# Rocket_PCB_Final.net
KiCad netlist of a schematic drawn in EasyEDA Pro
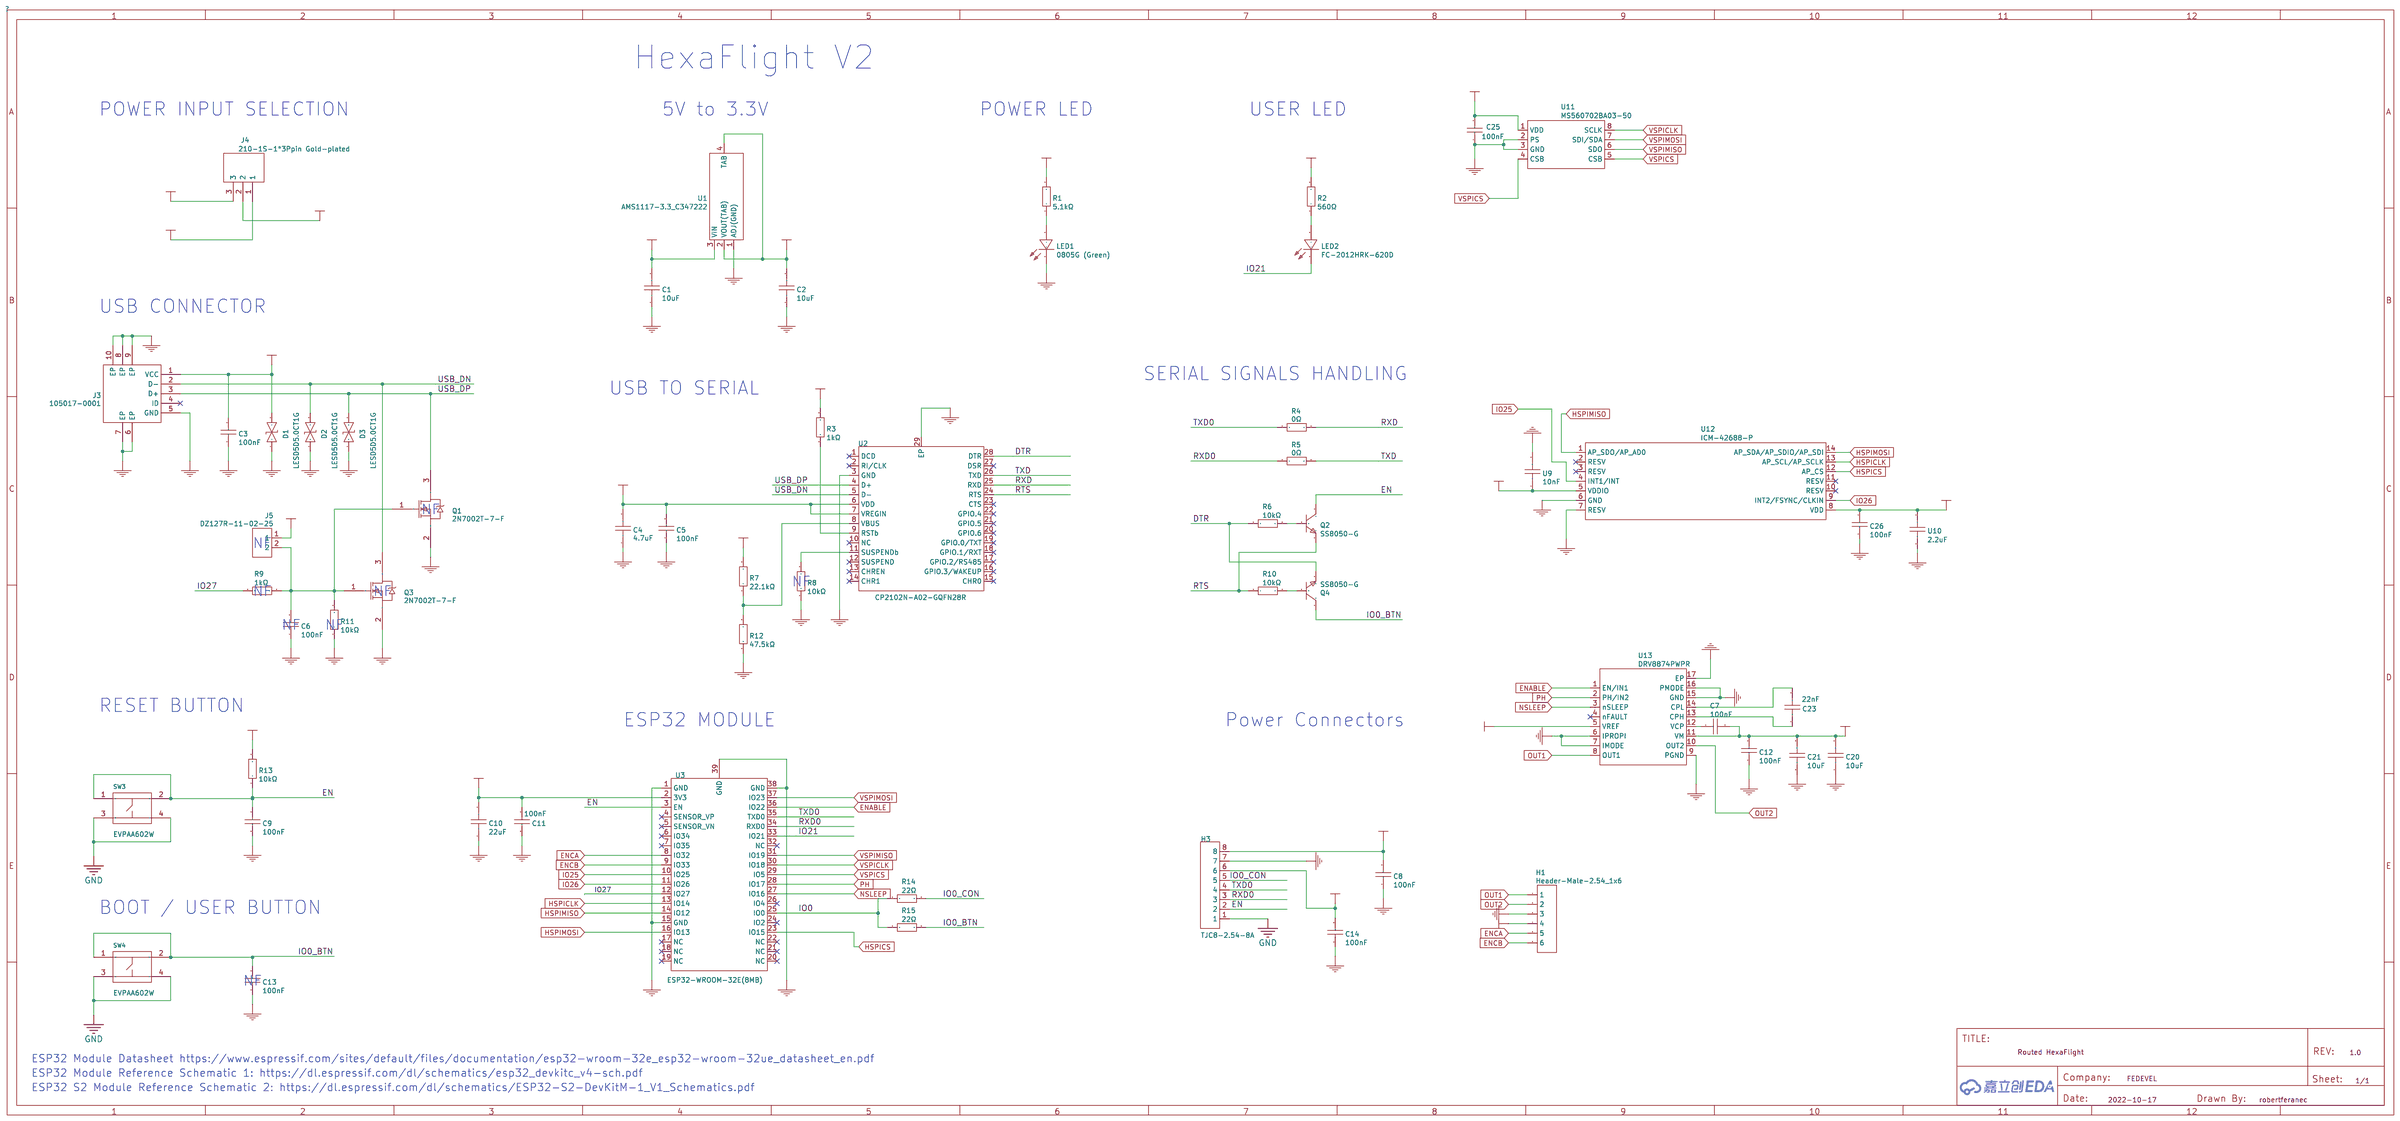
[diagram p0: schematic sheet]

(export (version "E")
  (design (tool "Eeschema 10.0.6"))
  (components
    (comp (ref "C1")
      (value "10uF")
      (footprint "easyedapro:C0402")
      (fields
        (field (name "Manufacturer Part") "CL05A106MP5NUNC")
        (field (name "Manufacturer") "Samsung Electro-Mechanics")
      )
      (libsource (lib "easyedapro") (part "10uF"))
    )
    (comp (ref "C2")
      (value "10uF")
      (footprint "easyedapro:C0402")
      (fields
        (field (name "Manufacturer Part") "CL05A106MP5NUNC")
        (field (name "Manufacturer") "Samsung Electro-Mechanics")
      )
      (libsource (lib "easyedapro") (part "10uF"))
    )
    (comp (ref "C3")
      (value "100nF")
      (footprint "easyedapro:C0402_NEW")
      (fields (field (name "Manufacturer Part") "CL05B104KO5NNNC") (field (name "Manufacturer") "SAMSUNG"))
      (libsource (lib "easyedapro") (part "100nF"))
    )
    (comp (ref "C4")
      (value "4.7uF")
      (footprint "easyedapro:C0402")
      (fields
        (field (name "Manufacturer Part") "CL05A475KP5NRNC")
        (field (name "Manufacturer") "Samsung Electro-Mechanics")
      )
      (libsource (lib "easyedapro") (part "4.7uF"))
    )
    (comp (ref "C5")
      (value "100nF")
      (footprint "easyedapro:C0402_NEW")
      (fields (field (name "Manufacturer Part") "CL05B104KO5NNNC") (field (name "Manufacturer") "SAMSUNG"))
      (libsource (lib "easyedapro") (part "100nF"))
    )
    (comp (ref "C6")
      (value "100nF")
      (footprint "easyedapro:C0402_NEW")
      (fields (field (name "Manufacturer Part") "CL05B104KO5NNNC") (field (name "Manufacturer") "SAMSUNG"))
      (libsource (lib "easyedapro") (part "100nF"))
    )
    (comp (ref "C7")
      (value "100nF")
      (footprint "easyedapro:C0402_NEW")
      (fields (field (name "Manufacturer Part") "CL05B104KO5NNNC") (field (name "Manufacturer") "SAMSUNG"))
      (libsource (lib "easyedapro") (part "100nF"))
    )
    (comp (ref "C8")
      (value "100nF")
      (footprint "easyedapro:C0402_NEW")
      (fields (field (name "Manufacturer Part") "CL05B104KO5NNNC") (field (name "Manufacturer") "SAMSUNG"))
      (libsource (lib "easyedapro") (part "100nF"))
    )
    (comp (ref "C9")
      (value "100nF")
      (footprint "easyedapro:C0402_NEW")
      (fields (field (name "Manufacturer Part") "CL05B104KO5NNNC") (field (name "Manufacturer") "SAMSUNG"))
      (libsource (lib "easyedapro") (part "100nF"))
    )
    (comp (ref "C10")
      (value "22uF")
      (footprint "easyedapro:C0805")
      (fields
        (field (name "Manufacturer Part") "CL21A226MAYNNNE")
        (field (name "Manufacturer") "Samsung Electro-Mechanics")
      )
      (libsource (lib "easyedapro") (part "22uF"))
    )
    (comp (ref "C11")
      (value "100nF")
      (footprint "easyedapro:C0402_NEW")
      (fields (field (name "Manufacturer Part") "CL05B104KO5NNNC") (field (name "Manufacturer") "SAMSUNG"))
      (libsource (lib "easyedapro") (part "100nF"))
    )
    (comp (ref "C12")
      (value "100nF")
      (footprint "easyedapro:C0402_NEW")
      (fields (field (name "Manufacturer Part") "CL05B104KO5NNNC") (field (name "Manufacturer") "SAMSUNG"))
      (libsource (lib "easyedapro") (part "100nF"))
    )
    (comp (ref "C13")
      (value "100nF")
      (footprint "easyedapro:C0402_NEW")
      (fields (field (name "Manufacturer Part") "CL05B104KO5NNNC") (field (name "Manufacturer") "SAMSUNG"))
      (libsource (lib "easyedapro") (part "100nF"))
    )
    (comp (ref "C14")
      (value "100nF")
      (footprint "easyedapro:C0402_NEW")
      (fields (field (name "Manufacturer Part") "CL05B104KO5NNNC") (field (name "Manufacturer") "SAMSUNG"))
      (libsource (lib "easyedapro") (part "100nF"))
    )
    (comp (ref "C20")
      (value "10uF")
      (footprint "easyedapro:C0402")
      (fields
        (field (name "Manufacturer Part") "CL05A106MP5NUNC")
        (field (name "Manufacturer") "Samsung Electro-Mechanics")
      )
      (libsource (lib "easyedapro") (part "10uF"))
    )
    (comp (ref "C21")
      (value "10uF")
      (footprint "easyedapro:C0402")
      (fields
        (field (name "Manufacturer Part") "CL05A106MP5NUNC")
        (field (name "Manufacturer") "Samsung Electro-Mechanics")
      )
      (libsource (lib "easyedapro") (part "10uF"))
    )
    (comp (ref "C23")
      (value "22nF")
      (footprint "easyedapro:C0603")
      (description "Capacitance:22nF Tolerance:±10% Tolerance:±10% Voltage Rating:50V Temperature Coefficient:X7R")
      (fields (field (name "Manufacturer Part") "CGA3E3X8R2A223KT0Y0N") (field (name "Manufacturer") "TDK"))
      (libsource (lib "easyedapro") (part "22nF"))
    )
    (comp (ref "C25")
      (value "100nF")
      (footprint "easyedapro:C0402_NEW")
      (fields (field (name "Manufacturer Part") "CL05B104KO5NNNC") (field (name "Manufacturer") "SAMSUNG"))
      (libsource (lib "easyedapro") (part "100nF"))
    )
    (comp (ref "C26")
      (value "100nF")
      (footprint "easyedapro:C0402_NEW")
      (fields (field (name "Manufacturer Part") "CL05B104KO5NNNC") (field (name "Manufacturer") "SAMSUNG"))
      (libsource (lib "easyedapro") (part "100nF"))
    )
    (comp (ref "D1")
      (value "LESD5D5.0CT1G")
      (footprint "easyedapro:SOD-523_L1.2-W0.8-LS1.6-BI")
      (fields (field (name "Manufacturer") "Leshan Radio") (field (name "Contributor") "LCSC"))
      (libsource (lib "easyedapro") (part "LESD5D5.0CT1G"))
    )
    (comp (ref "D2")
      (value "LESD5D5.0CT1G")
      (footprint "easyedapro:SOD-523_L1.2-W0.8-LS1.6-BI")
      (fields (field (name "Manufacturer") "Leshan Radio") (field (name "Contributor") "LCSC"))
      (libsource (lib "easyedapro") (part "LESD5D5.0CT1G"))
    )
    (comp (ref "D3")
      (value "LESD5D5.0CT1G")
      (footprint "easyedapro:SOD-523_L1.2-W0.8-LS1.6-BI")
      (fields (field (name "Manufacturer") "Leshan Radio") (field (name "Contributor") "LCSC"))
      (libsource (lib "easyedapro") (part "LESD5D5.0CT1G"))
    )
    (comp (ref "H1")
      (value "Header-Male-2.54_1x6")
      (footprint "easyedapro:HDR-TH_6P-P2.54-V-M-1")
      (fields (field (name "Manufacturer Part") "2.54-1x6P直针") (field (name "Manufacturer") "BOOMELE(博穆精密)"))
      (libsource (lib "easyedapro") (part "Header-Male-2.54_1x6"))
    )
    (comp (ref "H3")
      (value "TJC8-2.54-8A")
      (footprint "easyedapro:HDR-TH_8P-P2.54-V-M-4")
      (fields (field (name "Manufacturer") "DLL(德利)"))
      (libsource (lib "easyedapro") (part "TJC8-2.54-8A"))
    )
    (comp (ref "J3")
      (value "105017-0001")
      (footprint "easyedapro:MICRO-USB-SMD_105017-0001")
      (fields (field (name "Manufacturer") "MOLEX") (field (name "Contributor") "LCSC"))
      (libsource (lib "easyedapro") (part "105017-0001"))
    )
    (comp (ref "J4")
      (value "210-1S-1*3Ppin Gold-plated")
      (footprint "easyedapro:HDR-TH_3P-P1.27-V-M-1")
      (fields (field (name "Manufacturer") "Ckmtw") (field (name "Contributor") "LCSC"))
      (libsource (lib "easyedapro") (part "210-1S-1*3Ppin Gold-plated"))
    )
    (comp (ref "J5")
      (value "DZ127R-11-02-25")
      (footprint "easyedapro:HDR-TH_2P-P1.27-V-M")
      (fields (field (name "Manufacturer") "DEALON(德艺隆)") (field (name "Contributor") "LCSC"))
      (libsource (lib "easyedapro") (part "DZ127R-11-02-25"))
    )
    (comp (ref "LED1")
      (value "0805G (Green)")
      (footprint "easyedapro:LED0805-RD_GREEN")
      (fields (field (name "Manufacturer") "KENTO"))
      (libsource (lib "easyedapro") (part "0805G (Green)"))
    )
    (comp (ref "LED2")
      (value "FC-2012HRK-620D")
      (footprint "easyedapro:LED0805-RD_RED")
      (fields (field (name "Manufacturer") "NATIONSTAR"))
      (libsource (lib "easyedapro") (part "FC-2012HRK-620D"))
    )
    (comp (ref "Q1")
      (value "2N7002T-7-F")
      (footprint "easyedapro:SOT-523-3_L1.6-W0.8-P1.00-LS1.6-BR")
      (fields (field (name "Manufacturer") "DIODES") (field (name "Contributor") "LCSC"))
      (libsource (lib "easyedapro") (part "2N7002T-7-F"))
    )
    (comp (ref "Q2")
      (value "SS8050-G")
      (footprint "easyedapro:SOT-23-3_L2.9-W1.6-P1.90-LS2.8-BR")
      (fields (field (name "Manufacturer") "CJ(江苏长电/长晶)") (field (name "Contributor") "LCSC"))
      (libsource (lib "easyedapro") (part "SS8050-G"))
    )
    (comp (ref "Q3")
      (value "2N7002T-7-F")
      (footprint "easyedapro:SOT-523-3_L1.6-W0.8-P1.00-LS1.6-BR")
      (fields (field (name "Manufacturer") "DIODES") (field (name "Contributor") "LCSC"))
      (libsource (lib "easyedapro") (part "2N7002T-7-F"))
    )
    (comp (ref "Q4")
      (value "SS8050-G")
      (footprint "easyedapro:SOT-23-3_L2.9-W1.6-P1.90-LS2.8-BR")
      (fields (field (name "Manufacturer") "CJ(江苏长电/长晶)") (field (name "Contributor") "LCSC"))
      (libsource (lib "") (part "SS8050-G_1"))
    )
    (comp (ref "R1")
      (value "5.1kΩ")
      (footprint "easyedapro:R0402")
      (fields (field (name "Manufacturer Part") "0402WGF5101TCE") (field (name "Manufacturer") "UniOhm"))
      (libsource (lib "easyedapro") (part "5.1kΩ"))
    )
    (comp (ref "R2")
      (value "560Ω")
      (footprint "easyedapro:R0402")
      (fields (field (name "Manufacturer Part") "0402WGF5600TCE") (field (name "Manufacturer") "UniOhm"))
      (libsource (lib "easyedapro") (part "560Ω"))
    )
    (comp (ref "R3")
      (value "1kΩ")
      (footprint "easyedapro:R0402")
      (fields (field (name "Manufacturer Part") "0402WGF1001TCE") (field (name "Manufacturer") "UniOhm"))
      (libsource (lib "easyedapro") (part "1kΩ"))
    )
    (comp (ref "R4")
      (value "0Ω")
      (footprint "easyedapro:R0402")
      (fields (field (name "Manufacturer Part") "0402WGF0000TCE") (field (name "Manufacturer") "UniOhm"))
      (libsource (lib "easyedapro") (part "0Ω"))
    )
    (comp (ref "R5")
      (value "0Ω")
      (footprint "easyedapro:R0402")
      (fields (field (name "Manufacturer Part") "0402WGF0000TCE") (field (name "Manufacturer") "UniOhm"))
      (libsource (lib "easyedapro") (part "0Ω"))
    )
    (comp (ref "R6")
      (value "10kΩ")
      (footprint "easyedapro:R0402")
      (fields (field (name "Manufacturer Part") "0402WGF1002TCE") (field (name "Manufacturer") "UniOhm"))
      (libsource (lib "easyedapro") (part "10kΩ"))
    )
    (comp (ref "R7")
      (value "22.1kΩ")
      (footprint "easyedapro:R0402")
      (fields (field (name "Manufacturer Part") "0402WGF2212TCE") (field (name "Manufacturer") "UniOhm"))
      (libsource (lib "easyedapro") (part "22.1kΩ"))
    )
    (comp (ref "R8")
      (value "10kΩ")
      (footprint "easyedapro:R0402")
      (fields (field (name "Manufacturer Part") "0402WGF1002TCE") (field (name "Manufacturer") "UniOhm"))
      (libsource (lib "") (part "10kΩ_1"))
    )
    (comp (ref "R9")
      (value "1kΩ")
      (footprint "easyedapro:R0402")
      (fields (field (name "Manufacturer Part") "0402WGF1001TCE") (field (name "Manufacturer") "UniOhm"))
      (libsource (lib "") (part "1kΩ_1"))
    )
    (comp (ref "R10")
      (value "10kΩ")
      (footprint "easyedapro:R0402")
      (fields (field (name "Manufacturer Part") "0402WGF1002TCE") (field (name "Manufacturer") "UniOhm"))
      (libsource (lib "easyedapro") (part "10kΩ"))
    )
    (comp (ref "R11")
      (value "10kΩ")
      (footprint "easyedapro:R0402")
      (fields (field (name "Manufacturer Part") "0402WGF1002TCE") (field (name "Manufacturer") "UniOhm"))
      (libsource (lib "") (part "10kΩ_1"))
    )
    (comp (ref "R12")
      (value "47.5kΩ")
      (footprint "easyedapro:R0402")
      (fields (field (name "Manufacturer Part") "0402WGF4752TCE") (field (name "Manufacturer") "UniOhm"))
      (libsource (lib "easyedapro") (part "47.5kΩ"))
    )
    (comp (ref "R13")
      (value "10kΩ")
      (footprint "easyedapro:R0402")
      (fields (field (name "Manufacturer Part") "0402WGF1002TCE") (field (name "Manufacturer") "UniOhm"))
      (libsource (lib "") (part "10kΩ_1"))
    )
    (comp (ref "R14")
      (value "22Ω")
      (footprint "easyedapro:R0402")
      (fields (field (name "Manufacturer Part") "0402WGF220JTCE") (field (name "Manufacturer") "UniOhm"))
      (libsource (lib "easyedapro") (part "22Ω"))
    )
    (comp (ref "R15")
      (value "22Ω")
      (footprint "easyedapro:R0402")
      (fields (field (name "Manufacturer Part") "0402WGF220JTCE") (field (name "Manufacturer") "UniOhm"))
      (libsource (lib "easyedapro") (part "22Ω"))
    )
    (comp (ref "SW3")
      (value "EVPAA602W")
      (footprint "easyedapro:KEY-TH_4P-L3.5-W4.9-P2.80-LS4.3")
      (fields (field (name "Manufacturer") "PANASONIC(松下)"))
      (libsource (lib "easyedapro") (part "EVPAA602W"))
    )
    (comp (ref "SW4")
      (value "EVPAA602W")
      (footprint "easyedapro:KEY-TH_4P-L3.5-W4.9-P2.80-LS4.3")
      (fields (field (name "Manufacturer") "PANASONIC(松下)"))
      (libsource (lib "easyedapro") (part "EVPAA602W"))
    )
    (comp (ref "U1")
      (value "AMS1117-3.3_C347222")
      (footprint "easyedapro:SOT-223-4_L6.5-W3.5-P2.30-LS7.0-BR")
      (fields
        (field (name "Manufacturer Part") "AMS1117-3.3")
        (field (name "Manufacturer") "Youtai Semiconductor Co., Ltd.")
        (field (name "Contributor") "LCSC")
      )
      (libsource (lib "easyedapro") (part "AMS1117-3.3_C347222"))
    )
    (comp (ref "U2")
      (value "CP2102N-A02-GQFN28R")
      (footprint "easyedapro:QFN-28_L5.0-W5.0-P0.50-TL-EP3.3")
      (fields (field (name "Manufacturer") "SILICON LABS(芯科)") (field (name "Contributor") "LCSC"))
      (libsource (lib "easyedapro") (part "CP2102N-A02-GQFN28R"))
    )
    (comp (ref "U3")
      (value "ESP32-WROOM-32E(8MB)")
      (footprint "easyedapro:WIFI-SMD_ESP32-WROOM-32E")
      (fields (field (name "Manufacturer") "Espressif Systems") (field (name "Contributor") "LCSC"))
      (libsource (lib "easyedapro") (part "ESP32-WROOM-32E(8MB)"))
    )
    (comp (ref "U9")
      (value "10nF")
      (footprint "easyedapro:C0603")
      (fields
        (field (name "Manufacturer Part") "AC0603KRX7R7BB103")
        (field (name "Manufacturer") "YAGEO(国巨)")
      )
      (libsource (lib "easyedapro") (part "10nF"))
    )
    (comp (ref "U10")
      (value "2.2uF")
      (footprint "easyedapro:C0805")
      (fields
        (field (name "Manufacturer Part") "0805X225K250CT")
        (field (name "Manufacturer") "Walsin(华新科)")
        (field (name "Contributor") "lcsc")
      )
      (libsource (lib "easyedapro") (part "2.2uF"))
    )
    (comp (ref "U11")
      (value "MS560702BA03-50")
      (footprint "easyedapro:SENSOR-SMD_MS560702BA03-50")
      (fields (field (name "Manufacturer") "TE Connectivity(泰科电子)") (field (name "Contributor") "LCSC"))
      (libsource (lib "easyedapro") (part "MS560702BA03-50"))
    )
    (comp (ref "U12")
      (value "ICM-42688-P")
      (footprint "easyedapro:LGA-14_L3.0-W2.5-P0.50-TL")
      (fields (field (name "Manufacturer") "TDK InvenSense(应美盛)") (field (name "Contributor") "LCSC"))
      (libsource (lib "easyedapro") (part "ICM-42688-P"))
    )
    (comp (ref "U13")
      (value "DRV8874PWPR")
      (footprint "easyedapro:HTSSOP-16_L5.0-W4.4-P0.65-LS6.4-BL-EP")
      (fields (field (name "Manufacturer") "TI(德州仪器)") (field (name "Contributor") "LCSC"))
      (libsource (lib "easyedapro") (part "DRV8874PWPR"))
    )
  )
  (nets
    (net (code "1") (name "+3V3") (class "Default")
      (node (ref "C10") (pin "2") (pinfunction "2_2") (pintype "unspecified"))
      (node (ref "C11") (pin "2") (pinfunction "2_2") (pintype "input"))
      (node (ref "C2") (pin "2") (pinfunction "2_2") (pintype "unspecified"))
      (node (ref "C25") (pin "2") (pinfunction "2_2") (pintype "input"))
      (node (ref "C26") (pin "2") (pinfunction "2_2") (pintype "input"))
      (node (ref "C4") (pin "2") (pinfunction "2_2") (pintype "unspecified"))
      (node (ref "C5") (pin "2") (pinfunction "2_2") (pintype "input"))
      (node (ref "C8") (pin "2") (pinfunction "2_2") (pintype "input"))
      (node (ref "H3") (pin "8") (pinfunction "8_8") (pintype "unspecified"))
      (node (ref "J5") (pin "1") (pinfunction "1_1") (pintype "unspecified"))
      (node (ref "R1") (pin "2") (pinfunction "2_2") (pintype "input"))
      (node (ref "R13") (pin "2") (pinfunction "2_2") (pintype "input"))
      (node (ref "R2") (pin "2") (pinfunction "2_2") (pintype "input"))
      (node (ref "R3") (pin "2") (pinfunction "2_2") (pintype "input"))
      (node (ref "U1") (pin "2") (pinfunction "VOUT(TAB)_2") (pintype "unspecified"))
      (node (ref "U1") (pin "4") (pinfunction "TAB_4") (pintype "unspecified"))
      (node (ref "U10") (pin "1") (pinfunction "1_1") (pintype "unspecified"))
      (node (ref "U11") (pin "1") (pinfunction "VDD_1") (pintype "unspecified"))
      (node (ref "U12") (pin "5") (pinfunction "VDDIO_5") (pintype "unspecified"))
      (node (ref "U12") (pin "8") (pinfunction "VDD_8") (pintype "unspecified"))
      (node (ref "U13") (pin "5") (pinfunction "VREF_5") (pintype "unspecified"))
      (node (ref "U2") (pin "6") (pinfunction "VDD_6") (pintype "unspecified"))
      (node (ref "U2") (pin "7") (pinfunction "VREGIN_7") (pintype "unspecified"))
      (node (ref "U3") (pin "2") (pinfunction "3V3_2") (pintype "unspecified"))
      (node (ref "U9") (pin "1") (pinfunction "1_1") (pintype "unspecified"))
    )
    (net (code "2") (name "+5V") (class "Default")
      (node (ref "C1") (pin "2") (pinfunction "2_2") (pintype "unspecified"))
      (node (ref "C12") (pin "2") (pinfunction "2_2") (pintype "input"))
      (node (ref "C20") (pin "2") (pinfunction "2_2") (pintype "unspecified"))
      (node (ref "C21") (pin "2") (pinfunction "2_2") (pintype "unspecified"))
      (node (ref "C7") (pin "2") (pinfunction "2_2") (pintype "input"))
      (node (ref "H1") (pin "4") (pinfunction "4_4") (pintype "input"))
      (node (ref "J4") (pin "2") (pinfunction "2_2") (pintype "unspecified"))
      (node (ref "U1") (pin "3") (pinfunction "VIN_3") (pintype "unspecified"))
      (node (ref "U13") (pin "11") (pinfunction "VM_11") (pintype "unspecified"))
    )
    (net (code "3") (name "+5V_EXT") (class "Default")
      (node (ref "C14") (pin "2") (pinfunction "2_2") (pintype "input"))
      (node (ref "H3") (pin "6") (pinfunction "6_6") (pintype "unspecified"))
      (node (ref "J4") (pin "3") (pinfunction "3_3") (pintype "unspecified"))
    )
    (net (code "4") (name "+5V_VBUS") (class "Default")
      (node (ref "C3") (pin "2") (pinfunction "2_2") (pintype "input"))
      (node (ref "D1") (pin "2") (pinfunction "2_2") (pintype "unspecified"))
      (node (ref "J3") (pin "1") (pinfunction "VCC_1") (pintype "unspecified"))
      (node (ref "J4") (pin "1") (pinfunction "1_1") (pintype "unspecified"))
      (node (ref "R7") (pin "2") (pinfunction "2_2") (pintype "input"))
    )
    (net (code "5") (name "/DTR") (class "Default")
      (node (ref "Q4") (pin "2") (pinfunction "E_2") (pintype "input"))
      (node (ref "R6") (pin "1") (pinfunction "1_1") (pintype "input"))
      (node (ref "U2") (pin "28") (pinfunction "DTR_28") (pintype "unspecified"))
    )
    (net (code "6") (name "/EN") (class "Default")
      (node (ref "C9") (pin "2") (pinfunction "2_2") (pintype "input"))
      (node (ref "H3") (pin "2") (pinfunction "2_2") (pintype "unspecified"))
      (node (ref "Q2") (pin "3") (pinfunction "C_3") (pintype "input"))
      (node (ref "R13") (pin "1") (pinfunction "1_1") (pintype "input"))
      (node (ref "SW3") (pin "1") (pinfunction "2&apos;_1") (pintype "input"))
      (node (ref "SW3") (pin "2") (pinfunction "2_2") (pintype "input"))
      (node (ref "U3") (pin "3") (pinfunction "EN_3") (pintype "unspecified"))
    )
    (net (code "7") (name "/IO0") (class "Default")
      (node (ref "R14") (pin "1") (pinfunction "1_1") (pintype "input"))
      (node (ref "R15") (pin "1") (pinfunction "1_1") (pintype "input"))
      (node (ref "U3") (pin "25") (pinfunction "IO0_25") (pintype "unspecified"))
    )
    (net (code "8") (name "/IO0_BTN") (class "Default")
      (node (ref "C13") (pin "2") (pinfunction "2_2") (pintype "input"))
      (node (ref "Q4") (pin "3") (pinfunction "C_3") (pintype "input"))
      (node (ref "R15") (pin "2") (pinfunction "2_2") (pintype "input"))
      (node (ref "SW4") (pin "1") (pinfunction "2&apos;_1") (pintype "input"))
      (node (ref "SW4") (pin "2") (pinfunction "2_2") (pintype "input"))
    )
    (net (code "9") (name "/IO0_CON") (class "Default")
      (node (ref "H3") (pin "5") (pinfunction "5_5") (pintype "unspecified"))
      (node (ref "R14") (pin "2") (pinfunction "2_2") (pintype "input"))
    )
    (net (code "10") (name "/IO21") (class "Default")
      (node (ref "LED2") (pin "1") (pinfunction "-_1") (pintype "unspecified"))
      (node (ref "U3") (pin "33") (pinfunction "IO21_33") (pintype "unspecified"))
    )
    (net (code "11") (name "/IO27") (class "Default")
      (node (ref "R9") (pin "2") (pinfunction "2_2") (pintype "input"))
      (node (ref "U3") (pin "12") (pinfunction "IO27_12") (pintype "unspecified"))
    )
    (net (code "12") (name "/RTS") (class "Default")
      (node (ref "Q2") (pin "2") (pinfunction "E_2") (pintype "input"))
      (node (ref "R10") (pin "1") (pinfunction "1_1") (pintype "input"))
      (node (ref "U2") (pin "24") (pinfunction "RTS_24") (pintype "unspecified"))
    )
    (net (code "13") (name "/RXD") (class "Default")
      (node (ref "R4") (pin "2") (pinfunction "2_2") (pintype "input"))
      (node (ref "U2") (pin "25") (pinfunction "RXD_25") (pintype "unspecified"))
    )
    (net (code "14") (name "/RXD0") (class "Default")
      (node (ref "H3") (pin "3") (pinfunction "3_3") (pintype "unspecified"))
      (node (ref "R5") (pin "1") (pinfunction "1_1") (pintype "input"))
      (node (ref "U3") (pin "34") (pinfunction "RXD0_34") (pintype "unspecified"))
    )
    (net (code "15") (name "/TXD") (class "Default")
      (node (ref "R5") (pin "2") (pinfunction "2_2") (pintype "input"))
      (node (ref "U2") (pin "26") (pinfunction "TXD_26") (pintype "unspecified"))
    )
    (net (code "16") (name "/TXD0") (class "Default")
      (node (ref "H3") (pin "4") (pinfunction "4_4") (pintype "unspecified"))
      (node (ref "R4") (pin "1") (pinfunction "1_1") (pintype "input"))
      (node (ref "U3") (pin "35") (pinfunction "TXD0_35") (pintype "unspecified"))
    )
    (net (code "17") (name "/USB_DN") (class "Default")
      (node (ref "D2") (pin "2") (pinfunction "2_2") (pintype "unspecified"))
      (node (ref "J3") (pin "2") (pinfunction "D-_2") (pintype "unspecified"))
      (node (ref "Q3") (pin "3") (pinfunction "D_3") (pintype "unspecified"))
      (node (ref "U2") (pin "5") (pinfunction "D-_5") (pintype "unspecified"))
    )
    (net (code "18") (name "/USB_DP") (class "Default")
      (node (ref "D3") (pin "2") (pinfunction "2_2") (pintype "unspecified"))
      (node (ref "J3") (pin "3") (pinfunction "D+_3") (pintype "unspecified"))
      (node (ref "Q1") (pin "3") (pinfunction "D_3") (pintype "unspecified"))
      (node (ref "U2") (pin "4") (pinfunction "D+_4") (pintype "unspecified"))
    )
    (net (code "19") (name "ENABLE") (class "Default")
      (node (ref "U13") (pin "1") (pinfunction "EN/IN1_1") (pintype "unspecified"))
      (node (ref "U3") (pin "36") (pinfunction "IO22_36") (pintype "unspecified"))
    )
    (net (code "20") (name "ENCA") (class "Default")
      (node (ref "H1") (pin "5") (pinfunction "5_5") (pintype "input"))
      (node (ref "U3") (pin "8") (pinfunction "IO32_8") (pintype "unspecified"))
    )
    (net (code "21") (name "ENCB") (class "Default")
      (node (ref "H1") (pin "6") (pinfunction "6_6") (pintype "input"))
      (node (ref "U3") (pin "9") (pinfunction "IO33_9") (pintype "unspecified"))
    )
    (net (code "22") (name "GND") (class "Default")
      (node (ref "C1") (pin "1") (pinfunction "1_1") (pintype "unspecified"))
      (node (ref "C10") (pin "1") (pinfunction "1_1") (pintype "unspecified"))
      (node (ref "C11") (pin "1") (pinfunction "1_1") (pintype "input"))
      (node (ref "C12") (pin "1") (pinfunction "1_1") (pintype "input"))
      (node (ref "C13") (pin "1") (pinfunction "1_1") (pintype "input"))
      (node (ref "C14") (pin "1") (pinfunction "1_1") (pintype "input"))
      (node (ref "C2") (pin "1") (pinfunction "1_1") (pintype "unspecified"))
      (node (ref "C20") (pin "1") (pinfunction "1_1") (pintype "unspecified"))
      (node (ref "C21") (pin "1") (pinfunction "1_1") (pintype "unspecified"))
      (node (ref "C25") (pin "1") (pinfunction "1_1") (pintype "input"))
      (node (ref "C26") (pin "1") (pinfunction "1_1") (pintype "input"))
      (node (ref "C3") (pin "1") (pinfunction "1_1") (pintype "input"))
      (node (ref "C4") (pin "1") (pinfunction "1_1") (pintype "unspecified"))
      (node (ref "C5") (pin "1") (pinfunction "1_1") (pintype "input"))
      (node (ref "C6") (pin "1") (pinfunction "1_1") (pintype "input"))
      (node (ref "C8") (pin "1") (pinfunction "1_1") (pintype "input"))
      (node (ref "C9") (pin "1") (pinfunction "1_1") (pintype "input"))
      (node (ref "D1") (pin "1") (pinfunction "1_1") (pintype "unspecified"))
      (node (ref "D2") (pin "1") (pinfunction "1_1") (pintype "unspecified"))
      (node (ref "D3") (pin "1") (pinfunction "1_1") (pintype "unspecified"))
      (node (ref "H1") (pin "3") (pinfunction "3_3") (pintype "input"))
      (node (ref "H3") (pin "1") (pinfunction "1_1") (pintype "unspecified"))
      (node (ref "H3") (pin "7") (pinfunction "7_7") (pintype "unspecified"))
      (node (ref "J3") (pin "10") (pinfunction "EP_10") (pintype "unspecified"))
      (node (ref "J3") (pin "5") (pinfunction "GND_5") (pintype "unspecified"))
      (node (ref "J3") (pin "6") (pinfunction "EP_6") (pintype "unspecified"))
      (node (ref "J3") (pin "7") (pinfunction "EP_7") (pintype "unspecified"))
      (node (ref "J3") (pin "8") (pinfunction "EP_8") (pintype "unspecified"))
      (node (ref "J3") (pin "9") (pinfunction "EP_9") (pintype "unspecified"))
      (node (ref "LED1") (pin "1") (pinfunction "K_1") (pintype "unspecified"))
      (node (ref "Q1") (pin "2") (pinfunction "S_2") (pintype "unspecified"))
      (node (ref "Q3") (pin "2") (pinfunction "S_2") (pintype "unspecified"))
      (node (ref "R11") (pin "1") (pinfunction "1_1") (pintype "input"))
      (node (ref "R12") (pin "1") (pinfunction "1_1") (pintype "input"))
      (node (ref "R8") (pin "1") (pinfunction "1_1") (pintype "input"))
      (node (ref "SW3") (pin "3") (pinfunction "1&apos;_3") (pintype "input"))
      (node (ref "SW3") (pin "4") (pinfunction "1_4") (pintype "input"))
      (node (ref "SW4") (pin "3") (pinfunction "1&apos;_3") (pintype "input"))
      (node (ref "SW4") (pin "4") (pinfunction "1_4") (pintype "input"))
      (node (ref "U1") (pin "1") (pinfunction "ADJ(GND)_1") (pintype "unspecified"))
      (node (ref "U10") (pin "2") (pinfunction "2_2") (pintype "unspecified"))
      (node (ref "U11") (pin "2") (pinfunction "PS_2") (pintype "unspecified"))
      (node (ref "U11") (pin "3") (pinfunction "GND_3") (pintype "unspecified"))
      (node (ref "U12") (pin "6") (pinfunction "GND_6") (pintype "unspecified"))
      (node (ref "U12") (pin "7") (pinfunction "RESV_7") (pintype "unspecified"))
      (node (ref "U13") (pin "15") (pinfunction "GND_15") (pintype "unspecified"))
      (node (ref "U13") (pin "16") (pinfunction "PMODE_16") (pintype "unspecified"))
      (node (ref "U13") (pin "17") (pinfunction "EP_17") (pintype "unspecified"))
      (node (ref "U13") (pin "6") (pinfunction "IPROPI_6") (pintype "unspecified"))
      (node (ref "U13") (pin "7") (pinfunction "IMODE_7") (pintype "unspecified"))
      (node (ref "U13") (pin "9") (pinfunction "PGND_9") (pintype "unspecified"))
      (node (ref "U2") (pin "29") (pinfunction "EP_29") (pintype "unspecified"))
      (node (ref "U2") (pin "3") (pinfunction "GND_3") (pintype "unspecified"))
      (node (ref "U3") (pin "1") (pinfunction "GND_1") (pintype "unspecified"))
      (node (ref "U3") (pin "15") (pinfunction "GND_15") (pintype "unspecified"))
      (node (ref "U3") (pin "38") (pinfunction "GND_38") (pintype "unspecified"))
      (node (ref "U3") (pin "39") (pinfunction "GND_39") (pintype "unspecified"))
      (node (ref "U9") (pin "2") (pinfunction "2_2") (pintype "unspecified"))
    )
    (net (code "23") (name "HSPICLK") (class "Default")
      (node (ref "U12") (pin "13") (pinfunction "AP_SCL/AP_SCLK_13") (pintype "unspecified"))
      (node (ref "U3") (pin "13") (pinfunction "IO14_13") (pintype "unspecified"))
    )
    (net (code "24") (name "HSPICS") (class "Default")
      (node (ref "U12") (pin "12") (pinfunction "AP_CS_12") (pintype "unspecified"))
      (node (ref "U3") (pin "23") (pinfunction "IO15_23") (pintype "unspecified"))
    )
    (net (code "25") (name "HSPIMISO") (class "Default")
      (node (ref "U12") (pin "1") (pinfunction "AP_SDO/AP_AD0_1") (pintype "unspecified"))
      (node (ref "U3") (pin "14") (pinfunction "IO12_14") (pintype "unspecified"))
    )
    (net (code "26") (name "HSPIMOSI") (class "Default")
      (node (ref "U12") (pin "14") (pinfunction "AP_SDA/AP_SDIO/AP_SDI_14") (pintype "unspecified"))
      (node (ref "U3") (pin "16") (pinfunction "IO13_16") (pintype "unspecified"))
    )
    (net (code "27") (name "IO25") (class "Default")
      (node (ref "U12") (pin "4") (pinfunction "INT1/INT_4") (pintype "unspecified"))
      (node (ref "U3") (pin "10") (pinfunction "IO25_10") (pintype "unspecified"))
    )
    (net (code "28") (name "IO26") (class "Default")
      (node (ref "U12") (pin "9") (pinfunction "INT2/FSYNC/CLKIN_9") (pintype "unspecified"))
      (node (ref "U3") (pin "11") (pinfunction "IO26_11") (pintype "unspecified"))
    )
    (net (code "29") (name "NSLEEP") (class "Default")
      (node (ref "U13") (pin "3") (pinfunction "nSLEEP_3") (pintype "unspecified"))
      (node (ref "U3") (pin "27") (pinfunction "IO16_27") (pintype "unspecified"))
    )
    (net (code "30") (name "Net-(LED1-A)") (class "Default")
      (node (ref "LED1") (pin "2") (pinfunction "A_2") (pintype "unspecified"))
      (node (ref "R1") (pin "1") (pinfunction "1_1") (pintype "input"))
    )
    (net (code "31") (name "Net-(LED2-+)") (class "Default")
      (node (ref "LED2") (pin "2") (pinfunction "+_2") (pintype "unspecified"))
      (node (ref "R2") (pin "1") (pinfunction "1_1") (pintype "input"))
    )
    (net (code "32") (name "Net-(Q1-G)") (class "Default")
      (node (ref "C6") (pin "2") (pinfunction "2_2") (pintype "input"))
      (node (ref "J5") (pin "2") (pinfunction "2_2") (pintype "unspecified"))
      (node (ref "Q1") (pin "1") (pinfunction "G_1") (pintype "unspecified"))
      (node (ref "Q3") (pin "1") (pinfunction "G_1") (pintype "unspecified"))
      (node (ref "R11") (pin "2") (pinfunction "2_2") (pintype "input"))
      (node (ref "R9") (pin "1") (pinfunction "1_1") (pintype "input"))
    )
    (net (code "33") (name "Net-(Q2-B)") (class "Default")
      (node (ref "Q2") (pin "1") (pinfunction "B_1") (pintype "input"))
      (node (ref "R6") (pin "2") (pinfunction "2_2") (pintype "input"))
    )
    (net (code "34") (name "Net-(Q4-B)") (class "Default")
      (node (ref "Q4") (pin "1") (pinfunction "B_1") (pintype "input"))
      (node (ref "R10") (pin "2") (pinfunction "2_2") (pintype "input"))
    )
    (net (code "35") (name "Net-(U2-RSTb)") (class "Default")
      (node (ref "R3") (pin "1") (pinfunction "1_1") (pintype "input"))
      (node (ref "U2") (pin "9") (pinfunction "RSTb_9") (pintype "unspecified"))
    )
    (net (code "36") (name "Net-(U2-SUSPENDb)") (class "Default")
      (node (ref "R8") (pin "2") (pinfunction "2_2") (pintype "input"))
      (node (ref "U2") (pin "11") (pinfunction "SUSPENDb_11") (pintype "unspecified"))
    )
    (net (code "37") (name "Net-(U2-VBUS)") (class "Default")
      (node (ref "R12") (pin "2") (pinfunction "2_2") (pintype "input"))
      (node (ref "R7") (pin "1") (pinfunction "1_1") (pintype "input"))
      (node (ref "U2") (pin "8") (pinfunction "VBUS_8") (pintype "unspecified"))
    )
    (net (code "38") (name "Net-(U13-CPH)") (class "Default")
      (node (ref "C23") (pin "1") (pinfunction "1_1") (pintype "unspecified"))
      (node (ref "U13") (pin "13") (pinfunction "CPH_13") (pintype "unspecified"))
    )
    (net (code "39") (name "Net-(U13-CPL)") (class "Default")
      (node (ref "C23") (pin "2") (pinfunction "2_2") (pintype "unspecified"))
      (node (ref "U13") (pin "14") (pinfunction "CPL_14") (pintype "unspecified"))
    )
    (net (code "40") (name "Net-(U13-VCP)") (class "Default")
      (node (ref "C7") (pin "1") (pinfunction "1_1") (pintype "input"))
      (node (ref "U13") (pin "12") (pinfunction "VCP_12") (pintype "unspecified"))
    )
    (net (code "41") (name "OUT1") (class "Default")
      (node (ref "H1") (pin "1") (pinfunction "1_1") (pintype "input"))
      (node (ref "U13") (pin "8") (pinfunction "OUT1_8") (pintype "unspecified"))
    )
    (net (code "42") (name "OUT2") (class "Default")
      (node (ref "H1") (pin "2") (pinfunction "2_2") (pintype "input"))
      (node (ref "U13") (pin "10") (pinfunction "OUT2_10") (pintype "unspecified"))
    )
    (net (code "43") (name "PH") (class "Default")
      (node (ref "U13") (pin "2") (pinfunction "PH/IN2_2") (pintype "unspecified"))
      (node (ref "U3") (pin "28") (pinfunction "IO17_28") (pintype "unspecified"))
    )
    (net (code "44") (name "VSPICLK") (class "Default")
      (node (ref "U11") (pin "8") (pinfunction "SCLK_8") (pintype "unspecified"))
      (node (ref "U3") (pin "30") (pinfunction "IO18_30") (pintype "unspecified"))
    )
    (net (code "45") (name "VSPICS") (class "Default")
      (node (ref "U11") (pin "4") (pinfunction "CSB_4") (pintype "unspecified"))
      (node (ref "U11") (pin "5") (pinfunction "CSB_5") (pintype "unspecified"))
      (node (ref "U3") (pin "29") (pinfunction "IO5_29") (pintype "unspecified"))
    )
    (net (code "46") (name "VSPIMISO") (class "Default")
      (node (ref "U11") (pin "6") (pinfunction "SDO_6") (pintype "unspecified"))
      (node (ref "U3") (pin "31") (pinfunction "IO19_31") (pintype "unspecified"))
    )
    (net (code "47") (name "VSPIMOSI") (class "Default")
      (node (ref "U11") (pin "7") (pinfunction "SDI/SDA_7") (pintype "unspecified"))
      (node (ref "U3") (pin "37") (pinfunction "IO23_37") (pintype "unspecified"))
    )
    (net (code "48") (name "unconnected-(J3-ID-Pad4)") (class "Default")
      (node (ref "J3") (pin "4") (pinfunction "ID_4") (pintype "unspecified+no_connect"))
    )
    (net (code "49") (name "unconnected-(U2-CHR0-Pad15)") (class "Default")
      (node (ref "U2") (pin "15") (pinfunction "CHR0_15") (pintype "unspecified+no_connect"))
    )
    (net (code "50") (name "unconnected-(U2-CHR1-Pad14)") (class "Default")
      (node (ref "U2") (pin "14") (pinfunction "CHR1_14") (pintype "unspecified+no_connect"))
    )
    (net (code "51") (name "unconnected-(U2-CHREN-Pad13)") (class "Default")
      (node (ref "U2") (pin "13") (pinfunction "CHREN_13") (pintype "unspecified+no_connect"))
    )
    (net (code "52") (name "unconnected-(U2-CTS-Pad23)") (class "Default")
      (node (ref "U2") (pin "23") (pinfunction "CTS_23") (pintype "unspecified+no_connect"))
    )
    (net (code "53") (name "unconnected-(U2-DCD-Pad1)") (class "Default")
      (node (ref "U2") (pin "1") (pinfunction "DCD_1") (pintype "unspecified+no_connect"))
    )
    (net (code "54") (name "unconnected-(U2-DSR-Pad27)") (class "Default")
      (node (ref "U2") (pin "27") (pinfunction "DSR_27") (pintype "unspecified+no_connect"))
    )
    (net (code "55") (name "unconnected-(U2-GPIO.0{slash}TXT-Pad19)") (class "Default")
      (node (ref "U2") (pin "19") (pinfunction "GPIO.0/TXT_19") (pintype "unspecified+no_connect"))
    )
    (net (code "56") (name "unconnected-(U2-GPIO.1{slash}RXT-Pad18)") (class "Default")
      (node (ref "U2") (pin "18") (pinfunction "GPIO.1/RXT_18") (pintype "unspecified+no_connect"))
    )
    (net (code "57") (name "unconnected-(U2-GPIO.2{slash}RS485-Pad17)") (class "Default")
      (node (ref "U2") (pin "17") (pinfunction "GPIO.2/RS485_17") (pintype "unspecified+no_connect"))
    )
    (net (code "58") (name "unconnected-(U2-GPIO.3{slash}WAKEUP-Pad16)") (class "Default")
      (node (ref "U2") (pin "16") (pinfunction "GPIO.3/WAKEUP_16") (pintype "unspecified+no_connect"))
    )
    (net (code "59") (name "unconnected-(U2-GPIO.4-Pad22)") (class "Default")
      (node (ref "U2") (pin "22") (pinfunction "GPIO.4_22") (pintype "unspecified+no_connect"))
    )
    (net (code "60") (name "unconnected-(U2-GPIO.5-Pad21)") (class "Default")
      (node (ref "U2") (pin "21") (pinfunction "GPIO.5_21") (pintype "unspecified+no_connect"))
    )
    (net (code "61") (name "unconnected-(U2-GPIO.6-Pad20)") (class "Default")
      (node (ref "U2") (pin "20") (pinfunction "GPIO.6_20") (pintype "unspecified+no_connect"))
    )
    (net (code "62") (name "unconnected-(U2-NC-Pad10)") (class "Default")
      (node (ref "U2") (pin "10") (pinfunction "NC_10") (pintype "unspecified+no_connect"))
    )
    (net (code "63") (name "unconnected-(U2-RI{slash}CLK-Pad2)") (class "Default")
      (node (ref "U2") (pin "2") (pinfunction "RI/CLK_2") (pintype "unspecified+no_connect"))
    )
    (net (code "64") (name "unconnected-(U2-SUSPEND-Pad12)") (class "Default")
      (node (ref "U2") (pin "12") (pinfunction "SUSPEND_12") (pintype "unspecified+no_connect"))
    )
    (net (code "65") (name "unconnected-(U3-IO2-Pad24)") (class "Default")
      (node (ref "U3") (pin "24") (pinfunction "IO2_24") (pintype "unspecified+no_connect"))
    )
    (net (code "66") (name "unconnected-(U3-IO4-Pad26)") (class "Default")
      (node (ref "U3") (pin "26") (pinfunction "IO4_26") (pintype "unspecified+no_connect"))
    )
    (net (code "67") (name "unconnected-(U3-IO34-Pad6)") (class "Default")
      (node (ref "U3") (pin "6") (pinfunction "IO34_6") (pintype "unspecified+no_connect"))
    )
    (net (code "68") (name "unconnected-(U3-IO35-Pad7)") (class "Default")
      (node (ref "U3") (pin "7") (pinfunction "IO35_7") (pintype "unspecified+no_connect"))
    )
    (net (code "69") (name "unconnected-(U3-NC-Pad17)") (class "Default")
      (node (ref "U3") (pin "17") (pinfunction "NC_17") (pintype "unspecified+no_connect"))
    )
    (net (code "70") (name "unconnected-(U3-NC-Pad18)") (class "Default")
      (node (ref "U3") (pin "18") (pinfunction "NC_18") (pintype "unspecified+no_connect"))
    )
    (net (code "71") (name "unconnected-(U3-NC-Pad19)") (class "Default")
      (node (ref "U3") (pin "19") (pinfunction "NC_19") (pintype "unspecified+no_connect"))
    )
    (net (code "72") (name "unconnected-(U3-NC-Pad20)") (class "Default")
      (node (ref "U3") (pin "20") (pinfunction "NC_20") (pintype "unspecified+no_connect"))
    )
    (net (code "73") (name "unconnected-(U3-NC-Pad21)") (class "Default")
      (node (ref "U3") (pin "21") (pinfunction "NC_21") (pintype "unspecified+no_connect"))
    )
    (net (code "74") (name "unconnected-(U3-NC-Pad22)") (class "Default")
      (node (ref "U3") (pin "22") (pinfunction "NC_22") (pintype "unspecified+no_connect"))
    )
    (net (code "75") (name "unconnected-(U3-NC-Pad32)") (class "Default")
      (node (ref "U3") (pin "32") (pinfunction "NC_32") (pintype "unspecified+no_connect"))
    )
    (net (code "76") (name "unconnected-(U3-SENSOR_VN-Pad5)") (class "Default")
      (node (ref "U3") (pin "5") (pinfunction "SENSOR_VN_5") (pintype "unspecified+no_connect"))
    )
    (net (code "77") (name "unconnected-(U3-SENSOR_VP-Pad4)") (class "Default")
      (node (ref "U3") (pin "4") (pinfunction "SENSOR_VP_4") (pintype "unspecified+no_connect"))
    )
    (net (code "78") (name "unconnected-(U12-RESV-Pad2)") (class "Default")
      (node (ref "U12") (pin "2") (pinfunction "RESV_2") (pintype "unspecified+no_connect"))
    )
    (net (code "79") (name "unconnected-(U12-RESV-Pad3)") (class "Default")
      (node (ref "U12") (pin "3") (pinfunction "RESV_3") (pintype "unspecified+no_connect"))
    )
    (net (code "80") (name "unconnected-(U12-RESV-Pad10)") (class "Default")
      (node (ref "U12") (pin "10") (pinfunction "RESV_10") (pintype "unspecified+no_connect"))
    )
    (net (code "81") (name "unconnected-(U12-RESV-Pad11)") (class "Default")
      (node (ref "U12") (pin "11") (pinfunction "RESV_11") (pintype "unspecified+no_connect"))
    )
    (net (code "82") (name "unconnected-(U13-nFAULT-Pad4)") (class "Default")
      (node (ref "U13") (pin "4") (pinfunction "nFAULT_4") (pintype "unspecified+no_connect"))
    )
  )
)
